# HMC5883L.net
KiCad netlist of a schematic drawn in Altium Designer
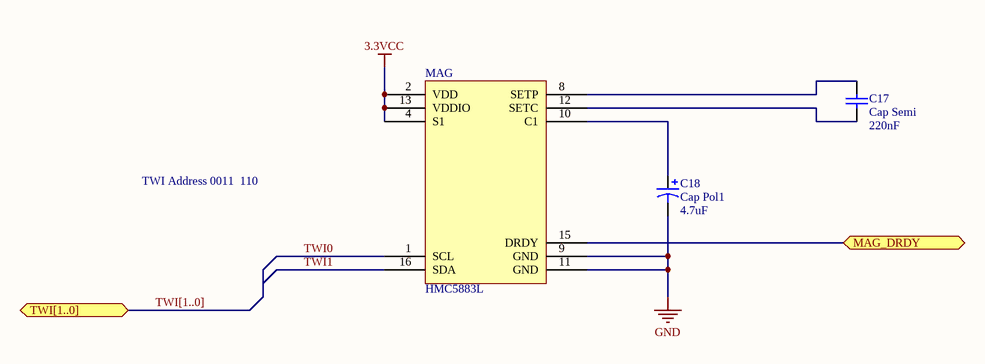
[diagram p0: HMC5883L.SchDoc]

(export (version "E")
  (design (tool "Eeschema 10.0.6"))
  (components
    (comp (ref "C17")
      (value "Cap Semi")
      (footprint "CAPC2012N")
      (description "Capacitor (Semiconductor SIM Model)")
      (fields (field (name "ALTIUM_VALUE") "220nF") (field (name "PUBLISHER") "Altium Limited"))
      (libsource (lib "Miscellaneous Devices") (part "Cap Semi"))
    )
    (comp (ref "C18")
      (value "Cap Pol1")
      (footprint "TC3528-1411")
      (description "Polarized Capacitor (Radial)")
      (fields (field (name "ALTIUM_VALUE") "4.7uF") (field (name "PUBLISHER") "Altium Limited"))
      (libsource (lib "Miscellaneous Devices") (part "Cap Pol1"))
    )
    (comp (ref "MAG")
      (value "HMC5883L")
      (footprint "HMC5883L - ECESHOP")
      (libsource (lib "HMC5883L") (part "HMC5883L"))
    )
  )
  (nets
    (net (code "1") (name "/MAG_DRDY") (class "Default")
      (node (ref "MAG") (pin "15") (pinfunction "DRDY_15") (pintype "passive"))
    )
    (net (code "2") (name "/TWI0") (class "Default")
      (node (ref "MAG") (pin "1") (pinfunction "SCL_1") (pintype "passive"))
    )
    (net (code "3") (name "/TWI1") (class "Default")
      (node (ref "MAG") (pin "16") (pinfunction "SDA_16") (pintype "passive"))
    )
    (net (code "5") (name "3.3VCC") (class "Default")
      (node (ref "MAG") (pin "13") (pinfunction "VDDIO_13") (pintype "passive"))
      (node (ref "MAG") (pin "2") (pinfunction "VDD_2") (pintype "passive"))
      (node (ref "MAG") (pin "4") (pinfunction "S1_4") (pintype "passive"))
    )
    (net (code "6") (name "GND") (class "Default")
      (node (ref "C18") (pin "2") (pinfunction "2_2") (pintype "passive"))
      (node (ref "MAG") (pin "11") (pinfunction "GND_11") (pintype "passive"))
      (node (ref "MAG") (pin "9") (pinfunction "GND_9") (pintype "passive"))
    )
    (net (code "7") (name "Net-(MAG-C1)") (class "Default")
      (node (ref "C18") (pin "1") (pinfunction "1_1") (pintype "passive"))
      (node (ref "MAG") (pin "10") (pinfunction "C1_10") (pintype "passive"))
    )
    (net (code "8") (name "Net-(MAG-SETC)") (class "Default")
      (node (ref "C17") (pin "2") (pinfunction "2_2") (pintype "passive"))
      (node (ref "MAG") (pin "12") (pinfunction "SETC_12") (pintype "passive"))
    )
    (net (code "9") (name "Net-(MAG-SETP)") (class "Default")
      (node (ref "C17") (pin "1") (pinfunction "1_1") (pintype "passive"))
      (node (ref "MAG") (pin "8") (pinfunction "SETP_8") (pintype "passive"))
    )
    (net (code "10") (name "unconnected-(MAG-NC-Pad3)") (class "Default")
      (node (ref "MAG") (pin "3") (pinfunction "NC_3") (pintype "passive"))
    )
    (net (code "11") (name "unconnected-(MAG-NC-Pad5)") (class "Default")
      (node (ref "MAG") (pin "5") (pinfunction "NC_5") (pintype "passive"))
    )
    (net (code "12") (name "unconnected-(MAG-NC-Pad6)") (class "Default")
      (node (ref "MAG") (pin "6") (pinfunction "NC_6") (pintype "passive"))
    )
    (net (code "13") (name "unconnected-(MAG-NC-Pad7)") (class "Default")
      (node (ref "MAG") (pin "7") (pinfunction "NC_7") (pintype "passive"))
    )
    (net (code "14") (name "unconnected-(MAG-NC-Pad14)") (class "Default")
      (node (ref "MAG") (pin "14") (pinfunction "NC_14") (pintype "passive"))
    )
  )
)
